# RoomSensor.net
KiCad netlist of a schematic drawn in Altium Designer
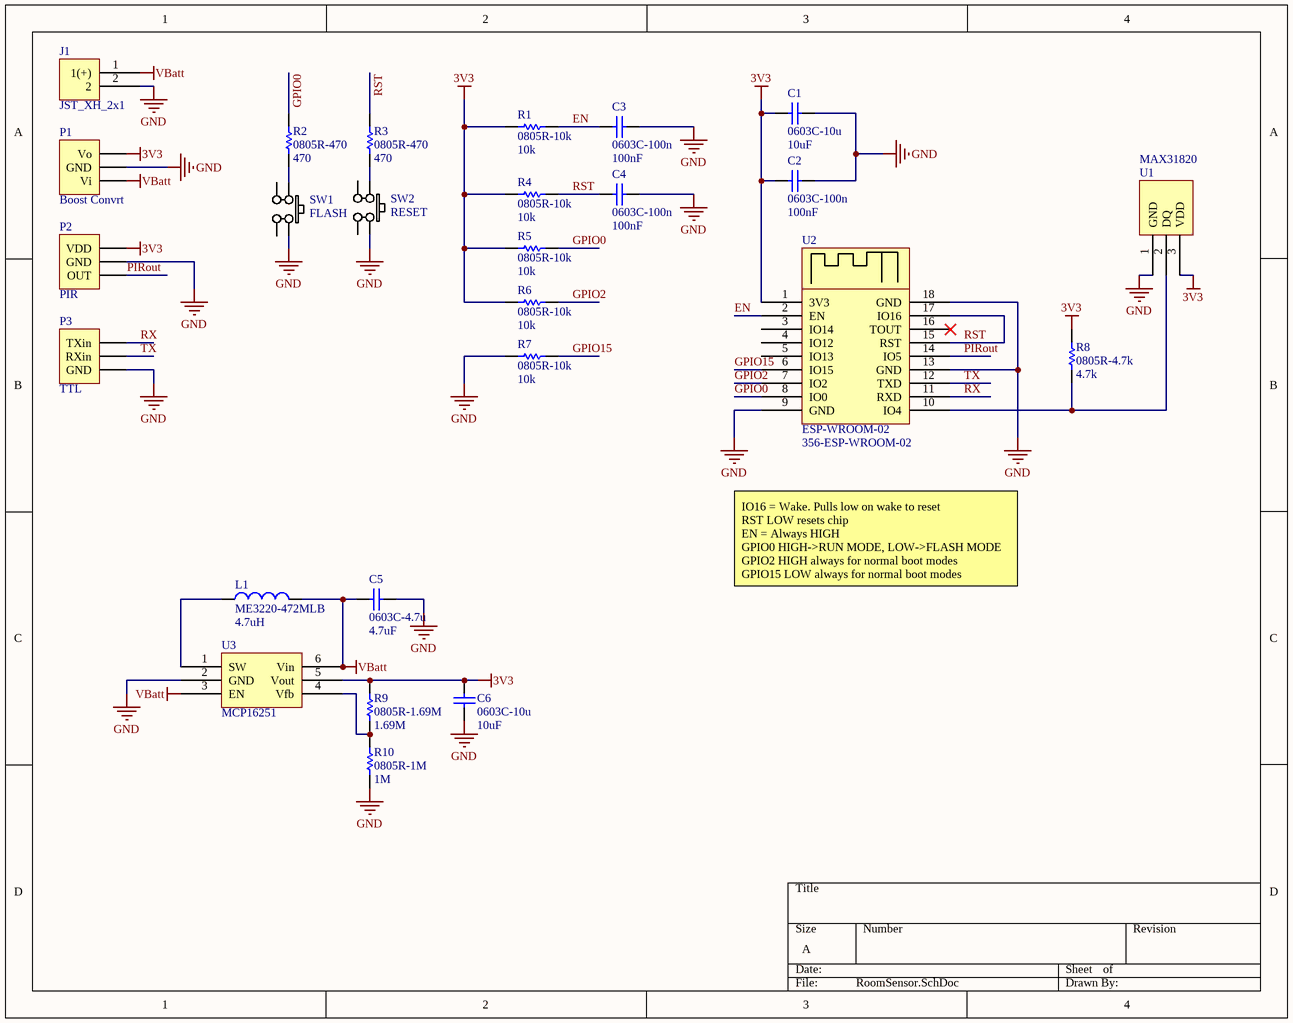
[diagram p0: RoomSensor.SchDoc]

(export (version "E")
  (design (tool "Eeschema 10.0.6"))
  (components
    (comp (ref "C1")
      (value "0603C-10u")
      (footprint "CHIP_0603")
      (fields (field (name "ALTIUM_VALUE") "10uF") (field (name "PUBLISHER") "Altium Limited"))
      (libsource (lib "Schlib1") (part "0603C-10u"))
    )
    (comp (ref "C2")
      (value "0603C-100n")
      (footprint "CHIP_0603")
      (fields (field (name "ALTIUM_VALUE") "100nF") (field (name "PUBLISHER") "Altium Limited"))
      (libsource (lib "Schlib1") (part "0603C-100n"))
    )
    (comp (ref "C3")
      (value "0603C-100n")
      (footprint "CHIP_0603")
      (fields (field (name "ALTIUM_VALUE") "100nF") (field (name "PUBLISHER") "Altium Limited"))
      (libsource (lib "Schlib1") (part "0603C-100n"))
    )
    (comp (ref "C4")
      (value "0603C-100n")
      (footprint "CHIP_0603")
      (fields (field (name "ALTIUM_VALUE") "100nF") (field (name "PUBLISHER") "Altium Limited"))
      (libsource (lib "Schlib1") (part "0603C-100n"))
    )
    (comp (ref "C5")
      (value "0603C-4.7u")
      (footprint "CHIP_0603")
      (fields (field (name "ALTIUM_VALUE") "4.7uF") (field (name "PUBLISHER") "Altium Limited"))
      (libsource (lib "Schlib1") (part "0603C-4.7u"))
    )
    (comp (ref "C6")
      (value "0603C-10u")
      (footprint "CHIP_0603")
      (fields (field (name "ALTIUM_VALUE") "10uF") (field (name "PUBLISHER") "Altium Limited"))
      (libsource (lib "Schlib1") (part "0603C-10u"))
    )
    (comp (ref "J1")
      (value "JST_XH_2x1")
      (footprint "JST_XH_2x1")
      (description "JST XH Header 2 pin, 1 row, 2.5mm pitch")
      (libsource (lib "Schlib1") (part "JST_XH_2x1"))
    )
    (comp (ref "L1")
      (value "ME3220-472MLB")
      (footprint "ME3220-472MLB")
      (fields (field (name "ALTIUM_VALUE") "4.7uH") (field (name "PUBLISHER") "Altium Limited"))
      (libsource (lib "Schlib1") (part "ME3220-472MLB"))
    )
    (comp (ref "P1")
      (value "Boost Convrt")
      (footprint "3x1 Header")
      (description "Header, 3-Pin")
      (fields (field (name "PUBLISHER") "Altium Limited"))
      (libsource (lib "") (part "Header 3_1"))
    )
    (comp (ref "P2")
      (value "PIR")
      (footprint "HDR1X3")
      (description "Header, 3-Pin")
      (fields (field (name "PUBLISHER") "Altium Limited"))
      (libsource (lib "Miscellaneous Connectors") (part "Header 3"))
    )
    (comp (ref "P3")
      (value "TTL")
      (footprint "3x1 Header")
      (description "Header, 3-Pin, Right Angle")
      (fields (field (name "PUBLISHER") "Altium Limited"))
      (libsource (lib "Miscellaneous Connectors") (part "Header 3H"))
    )
    (comp (ref "R1")
      (value "0805R-10k")
      (footprint "Chip_0805")
      (fields (field (name "ALTIUM_VALUE") "10k") (field (name "PUBLISHER") "Altium Limited"))
      (libsource (lib "Schlib1") (part "0805R-10k"))
    )
    (comp (ref "R2")
      (value "0805R-470")
      (footprint "Chip_0805")
      (fields (field (name "ALTIUM_VALUE") "470") (field (name "PUBLISHER") "Altium Limited"))
      (libsource (lib "Schlib1") (part "0805R-470"))
    )
    (comp (ref "R3")
      (value "0805R-470")
      (footprint "Chip_0805")
      (fields (field (name "ALTIUM_VALUE") "470") (field (name "PUBLISHER") "Altium Limited"))
      (libsource (lib "Schlib1") (part "0805R-470"))
    )
    (comp (ref "R4")
      (value "0805R-10k")
      (footprint "Chip_0805")
      (fields (field (name "ALTIUM_VALUE") "10k") (field (name "PUBLISHER") "Altium Limited"))
      (libsource (lib "Schlib1") (part "0805R-10k"))
    )
    (comp (ref "R5")
      (value "0805R-10k")
      (footprint "Chip_0805")
      (fields (field (name "ALTIUM_VALUE") "10k") (field (name "PUBLISHER") "Altium Limited"))
      (libsource (lib "Schlib1") (part "0805R-10k"))
    )
    (comp (ref "R6")
      (value "0805R-10k")
      (footprint "Chip_0805")
      (fields (field (name "ALTIUM_VALUE") "10k") (field (name "PUBLISHER") "Altium Limited"))
      (libsource (lib "Schlib1") (part "0805R-10k"))
    )
    (comp (ref "R7")
      (value "0805R-10k")
      (footprint "Chip_0805")
      (fields (field (name "ALTIUM_VALUE") "10k") (field (name "PUBLISHER") "Altium Limited"))
      (libsource (lib "Schlib1") (part "0805R-10k"))
    )
    (comp (ref "R8")
      (value "0805R-4.7k")
      (footprint "Chip_0805")
      (fields (field (name "ALTIUM_VALUE") "4.7k") (field (name "PUBLISHER") "Altium Limited"))
      (libsource (lib "Schlib1") (part "0805R-4.7k"))
    )
    (comp (ref "R9")
      (value "0805R-1.69M")
      (footprint "Chip_0805")
      (fields (field (name "ALTIUM_VALUE") "1.69M") (field (name "PUBLISHER") "Altium Limited"))
      (libsource (lib "Schlib1") (part "0805R-1.69M"))
    )
    (comp (ref "R10")
      (value "0805R-1M")
      (footprint "Chip_0805")
      (fields (field (name "ALTIUM_VALUE") "1M") (field (name "PUBLISHER") "Altium Limited"))
      (libsource (lib "Schlib1") (part "0805R-1M"))
    )
    (comp (ref "SW1")
      (value "FLASH")
      (footprint "TL3305AF260QG")
      (description "TL3305AF260QG")
      (libsource (lib "Schlib1") (part "SW_PB"))
    )
    (comp (ref "SW2")
      (value "RESET")
      (footprint "TL3305AF260QG")
      (description "TL3305AF260QG")
      (libsource (lib "Schlib1") (part "SW_PB"))
    )
    (comp (ref "U1") (value "MAX31820") (footprint "TO-92") (libsource (lib "Schlib1") (part "MAX31820")))
    (comp (ref "U2")
      (value "ESP-WROOM-02")
      (footprint "ESP-WROOM-02")
      (fields (field (name "SUPPLIER PART NUMBER 1") "356-ESP-WROOM-02"))
      (libsource (lib "Schlib1") (part "ESP-WROOM-02"))
    )
    (comp (ref "U3")
      (value "MCP16251")
      (footprint "SOT23 MCP16251")
      (libsource (lib "Schlib1") (part "MCP16251T"))
    )
  )
  (nets
    (net (code "1") (name "/EN") (class "Default")
      (node (ref "C3") (pin "1") (pinfunction "1_1") (pintype "passive"))
      (node (ref "R1") (pin "2") (pinfunction "2_2") (pintype "passive"))
      (node (ref "U2") (pin "2") (pinfunction "EN_2") (pintype "passive"))
    )
    (net (code "2") (name "/GPIO0") (class "Default")
      (node (ref "R2") (pin "2") (pinfunction "2_2") (pintype "passive"))
      (node (ref "R5") (pin "2") (pinfunction "2_2") (pintype "passive"))
      (node (ref "U2") (pin "8") (pinfunction "IO0_8") (pintype "passive"))
    )
    (net (code "3") (name "/GPIO2") (class "Default")
      (node (ref "R6") (pin "2") (pinfunction "2_2") (pintype "passive"))
      (node (ref "U2") (pin "7") (pinfunction "IO2_7") (pintype "passive"))
    )
    (net (code "4") (name "/GPIO15") (class "Default")
      (node (ref "R7") (pin "2") (pinfunction "2_2") (pintype "passive"))
      (node (ref "U2") (pin "6") (pinfunction "IO15_6") (pintype "passive"))
    )
    (net (code "5") (name "/PIRout") (class "Default")
      (node (ref "P2") (pin "3") (pinfunction "OUT_3") (pintype "passive"))
      (node (ref "U2") (pin "14") (pinfunction "IO5_14") (pintype "passive"))
    )
    (net (code "6") (name "/RST") (class "Default")
      (node (ref "C4") (pin "1") (pinfunction "1_1") (pintype "passive"))
      (node (ref "R3") (pin "2") (pinfunction "2_2") (pintype "passive"))
      (node (ref "R4") (pin "2") (pinfunction "2_2") (pintype "passive"))
      (node (ref "U2") (pin "15") (pinfunction "RST_15") (pintype "passive"))
      (node (ref "U2") (pin "17") (pinfunction "IO16_17") (pintype "passive"))
    )
    (net (code "7") (name "/RX") (class "Default")
      (node (ref "P3") (pin "1") (pinfunction "TXin_1") (pintype "passive"))
      (node (ref "U2") (pin "11") (pinfunction "RXD_11") (pintype "passive"))
    )
    (net (code "8") (name "/TX") (class "Default")
      (node (ref "P3") (pin "2") (pinfunction "RXin_2") (pintype "passive"))
      (node (ref "U2") (pin "12") (pinfunction "TXD_12") (pintype "passive"))
    )
    (net (code "9") (name "3V3") (class "Default")
      (node (ref "C1") (pin "1") (pinfunction "1_1") (pintype "passive"))
      (node (ref "C2") (pin "1") (pinfunction "1_1") (pintype "passive"))
      (node (ref "C6") (pin "2") (pinfunction "2_2") (pintype "passive"))
      (node (ref "P1") (pin "1") (pinfunction "Vo_1") (pintype "passive"))
      (node (ref "P2") (pin "1") (pinfunction "VDD_1") (pintype "passive"))
      (node (ref "R1") (pin "1") (pinfunction "1_1") (pintype "passive"))
      (node (ref "R4") (pin "1") (pinfunction "1_1") (pintype "passive"))
      (node (ref "R5") (pin "1") (pinfunction "1_1") (pintype "passive"))
      (node (ref "R6") (pin "1") (pinfunction "1_1") (pintype "passive"))
      (node (ref "R8") (pin "2") (pinfunction "2_2") (pintype "passive"))
      (node (ref "R9") (pin "2") (pinfunction "2_2") (pintype "passive"))
      (node (ref "U1") (pin "3") (pinfunction "VDD_3") (pintype "passive"))
      (node (ref "U2") (pin "1") (pinfunction "3V3_1") (pintype "passive"))
      (node (ref "U3") (pin "5") (pinfunction "Vout_5") (pintype "passive"))
    )
    (net (code "10") (name "GND") (class "Default")
      (node (ref "C1") (pin "2") (pinfunction "2_2") (pintype "passive"))
      (node (ref "C2") (pin "2") (pinfunction "2_2") (pintype "passive"))
      (node (ref "C3") (pin "2") (pinfunction "2_2") (pintype "passive"))
      (node (ref "C4") (pin "2") (pinfunction "2_2") (pintype "passive"))
      (node (ref "C5") (pin "2") (pinfunction "2_2") (pintype "passive"))
      (node (ref "C6") (pin "1") (pinfunction "1_1") (pintype "passive"))
      (node (ref "J1") (pin "2") (pinfunction "2_2") (pintype "passive"))
      (node (ref "P1") (pin "2") (pinfunction "GND_2") (pintype "passive"))
      (node (ref "P2") (pin "2") (pinfunction "GND_2") (pintype "passive"))
      (node (ref "P3") (pin "3") (pinfunction "GND_3") (pintype "passive"))
      (node (ref "R10") (pin "1") (pinfunction "1_1") (pintype "passive"))
      (node (ref "R7") (pin "1") (pinfunction "1_1") (pintype "passive"))
      (node (ref "SW1") (pin "3") (pintype "passive"))
      (node (ref "SW2") (pin "3") (pintype "passive"))
      (node (ref "U1") (pin "1") (pinfunction "GND_1") (pintype "passive"))
      (node (ref "U2") (pin "13") (pinfunction "GND_13") (pintype "passive"))
      (node (ref "U2") (pin "18") (pinfunction "GND_18") (pintype "passive"))
      (node (ref "U2") (pin "9") (pinfunction "GND_9") (pintype "passive"))
      (node (ref "U3") (pin "2") (pinfunction "GND_2") (pintype "passive"))
    )
    (net (code "11") (name "Net-(R2-Pad1)") (class "Default")
      (node (ref "R2") (pin "1") (pinfunction "1_1") (pintype "passive"))
      (node (ref "SW1") (pin "1") (pintype "passive"))
    )
    (net (code "12") (name "Net-(R3-Pad1)") (class "Default")
      (node (ref "R3") (pin "1") (pinfunction "1_1") (pintype "passive"))
      (node (ref "SW2") (pin "1") (pintype "passive"))
    )
    (net (code "13") (name "Net-(U1-DQ)") (class "Default")
      (node (ref "R8") (pin "1") (pinfunction "1_1") (pintype "passive"))
      (node (ref "U1") (pin "2") (pinfunction "DQ_2") (pintype "passive"))
      (node (ref "U2") (pin "10") (pinfunction "IO4_10") (pintype "passive"))
    )
    (net (code "14") (name "Net-(U3-SW)") (class "Default")
      (node (ref "L1") (pin "1") (pinfunction "1_1") (pintype "passive"))
      (node (ref "U3") (pin "1") (pinfunction "SW_1") (pintype "passive"))
    )
    (net (code "15") (name "Net-(U3-Vfb)") (class "Default")
      (node (ref "R10") (pin "2") (pinfunction "2_2") (pintype "passive"))
      (node (ref "R9") (pin "1") (pinfunction "1_1") (pintype "passive"))
      (node (ref "U3") (pin "4") (pinfunction "Vfb_4") (pintype "passive"))
    )
    (net (code "16") (name "VBatt") (class "Default")
      (node (ref "C5") (pin "1") (pinfunction "1_1") (pintype "passive"))
      (node (ref "J1") (pin "1") (pinfunction "1(+)_1") (pintype "passive"))
      (node (ref "L1") (pin "2") (pinfunction "2_2") (pintype "passive"))
      (node (ref "P1") (pin "3") (pinfunction "Vi_3") (pintype "passive"))
      (node (ref "U3") (pin "3") (pinfunction "EN_3") (pintype "passive"))
      (node (ref "U3") (pin "6") (pinfunction "Vin_6") (pintype "passive"))
    )
    (net (code "17") (name "unconnected-(SW1-Pad2)") (class "Default")
      (node (ref "SW1") (pin "2") (pintype "passive"))
    )
    (net (code "18") (name "unconnected-(SW1-Pad4)") (class "Default")
      (node (ref "SW1") (pin "4") (pintype "passive"))
    )
    (net (code "19") (name "unconnected-(SW2-Pad2)") (class "Default")
      (node (ref "SW2") (pin "2") (pintype "passive"))
    )
    (net (code "20") (name "unconnected-(SW2-Pad4)") (class "Default")
      (node (ref "SW2") (pin "4") (pintype "passive"))
    )
    (net (code "21") (name "unconnected-(U2-IO12-Pad4)") (class "Default")
      (node (ref "U2") (pin "4") (pinfunction "IO12_4") (pintype "passive"))
    )
    (net (code "22") (name "unconnected-(U2-IO13-Pad5)") (class "Default")
      (node (ref "U2") (pin "5") (pinfunction "IO13_5") (pintype "passive"))
    )
    (net (code "23") (name "unconnected-(U2-IO14-Pad3)") (class "Default")
      (node (ref "U2") (pin "3") (pinfunction "IO14_3") (pintype "passive"))
    )
    (net (code "24") (name "unconnected-(U2-TOUT-Pad16)") (class "Default")
      (node (ref "U2") (pin "16") (pinfunction "TOUT_16") (pintype "passive+no_connect"))
    )
  )
)
